# FC30_v10.net
KiCad netlist of a schematic drawn in EAGLE
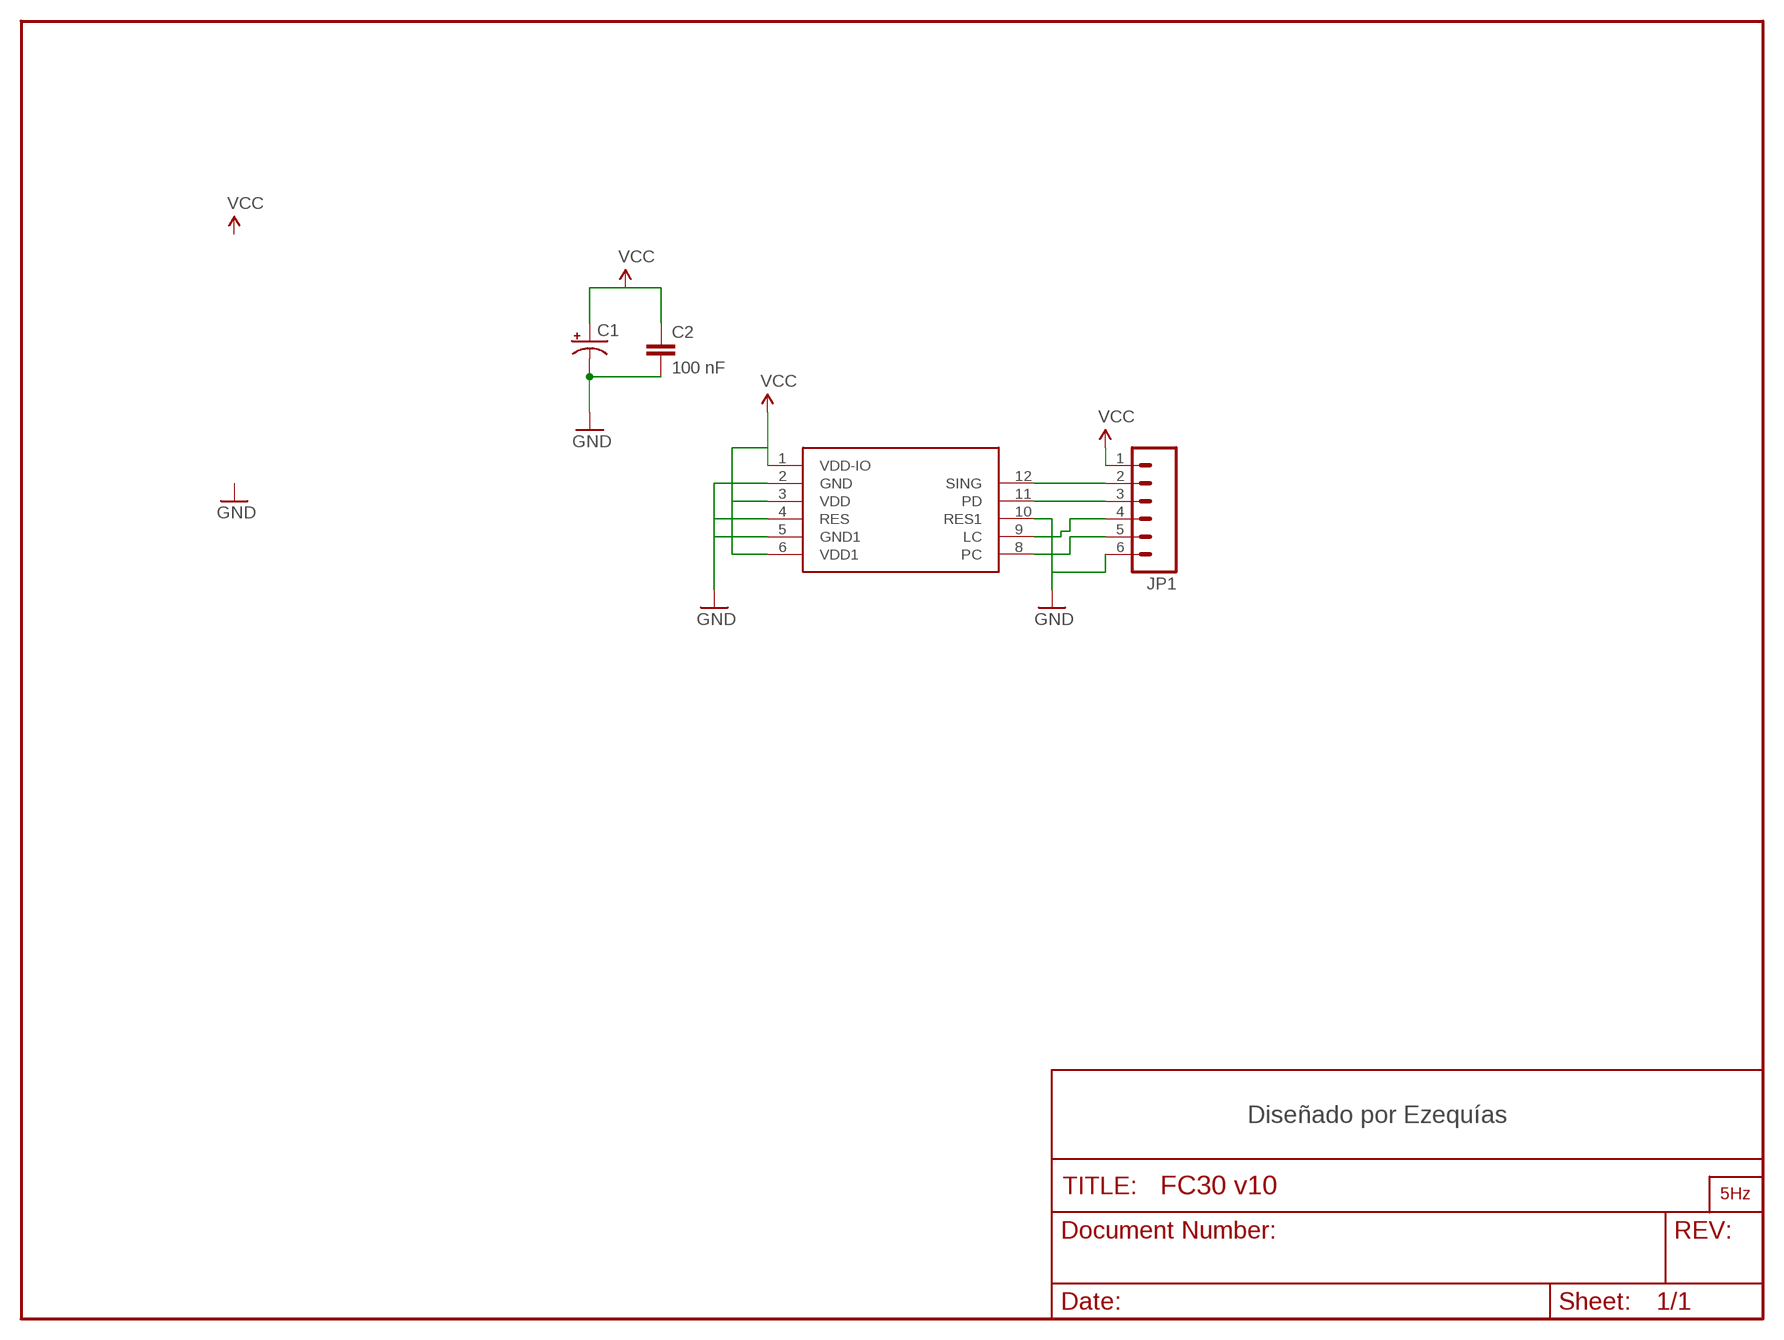
[diagram p0: schematic, sheet 1]

(export (version "E")
  (design (tool "Eeschema 10.0.6"))
  (components
    (comp (ref "C1")
      (value "CAP_POL1206")
      (footprint "eagle-import:EIA3216")
      (libsource (lib "eagle-import") (part "CAP_POL1206"))
    )
    (comp (ref "C2")
      (value "100 nF")
      (footprint "eagle-import:0603-CAP")
      (libsource (lib "eagle-import") (part "CAP0603-CAP"))
    )
    (comp (ref "JP1")
      (value "M06SIP")
      (footprint "eagle-import:1X06")
      (libsource (lib "eagle-import") (part "M06SIP"))
    )
    (comp (ref "U$1")
      (value "FC30")
      (footprint "eagle-import:LGA-14")
      (libsource (lib "eagle-import") (part "FC30"))
    )
    (comp (ref "U$2")
      (value "LOGO2_SILK5MM")
      (footprint "eagle-import:LOGO2_5MM")
      (libsource (lib "eagle-import") (part "LOGO2_SILK5MM"))
    )
  )
  (nets
    (net (code "1") (name "GND") (class "Default")
      (node (ref "C1") (pin "C") (pinfunction "-_C") (pintype "passive"))
      (node (ref "C2") (pin "2") (pinfunction "2_2") (pintype "passive"))
      (node (ref "JP1") (pin "6") (pinfunction "6_6") (pintype "passive"))
      (node (ref "U$1") (pin "10") (pinfunction "RES1_10") (pintype "bidirectional"))
      (node (ref "U$1") (pin "2") (pinfunction "GND_2") (pintype "bidirectional"))
      (node (ref "U$1") (pin "4") (pinfunction "RES_4") (pintype "bidirectional"))
      (node (ref "U$1") (pin "5") (pinfunction "GND1_5") (pintype "bidirectional"))
    )
    (net (code "2") (name "Net-(U$1-LC)") (class "Default")
      (node (ref "JP1") (pin "4") (pinfunction "4_4") (pintype "passive"))
      (node (ref "U$1") (pin "9") (pinfunction "LC_9") (pintype "bidirectional"))
    )
    (net (code "3") (name "Net-(U$1-PC)") (class "Default")
      (node (ref "JP1") (pin "5") (pinfunction "5_5") (pintype "passive"))
      (node (ref "U$1") (pin "8") (pinfunction "PC_8") (pintype "bidirectional"))
    )
    (net (code "4") (name "Net-(U$1-PD)") (class "Default")
      (node (ref "JP1") (pin "3") (pinfunction "3_3") (pintype "passive"))
      (node (ref "U$1") (pin "11") (pinfunction "PD_11") (pintype "bidirectional"))
    )
    (net (code "5") (name "Net-(U$1-SING)") (class "Default")
      (node (ref "JP1") (pin "2") (pinfunction "2_2") (pintype "passive"))
      (node (ref "U$1") (pin "12") (pinfunction "SING_12") (pintype "bidirectional"))
    )
    (net (code "6") (name "VCC") (class "Default")
      (node (ref "C1") (pin "A") (pinfunction "+_A") (pintype "passive"))
      (node (ref "C2") (pin "1") (pinfunction "1_1") (pintype "passive"))
      (node (ref "JP1") (pin "1") (pinfunction "1_1") (pintype "passive"))
      (node (ref "U$1") (pin "1") (pinfunction "VDD-IO_1") (pintype "bidirectional"))
      (node (ref "U$1") (pin "3") (pinfunction "VDD_3") (pintype "bidirectional"))
      (node (ref "U$1") (pin "6") (pinfunction "VDD1_6") (pintype "bidirectional"))
    )
  )
)
